# SCH9_BBB_Eth.net
KiCad netlist of a schematic drawn in Altium Designer
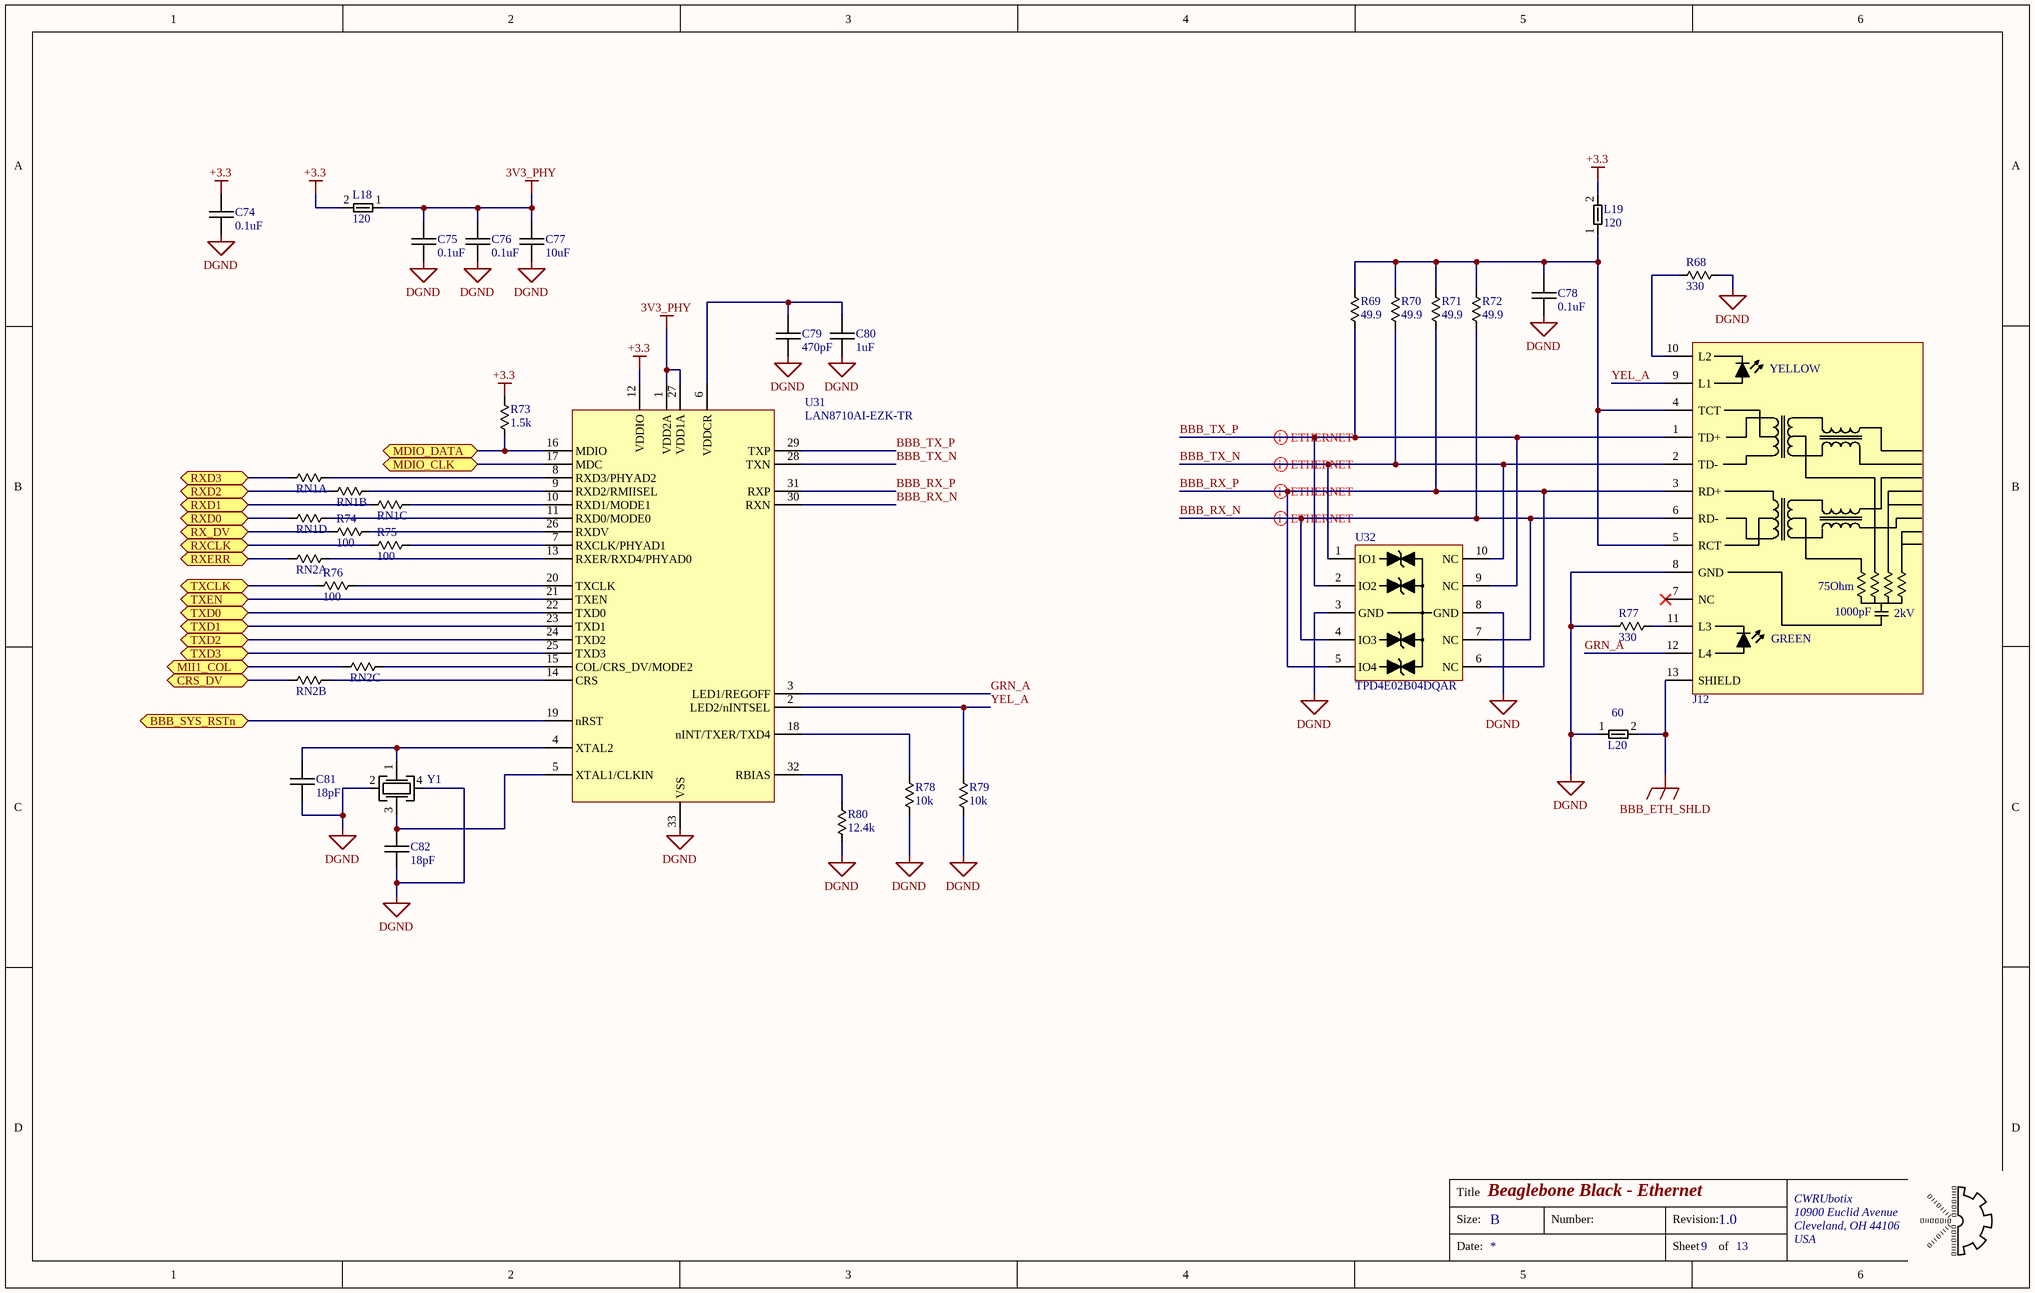
[diagram p0: SCH9_BBB_Eth.SchDoc]

(export (version "E")
  (design (tool "Eeschema 10.0.6"))
  (components
    (comp (ref "C74")
      (value "0.1uF")
      (footprint "chip_0603")
      (description "CAP, 0.1uF, ±10%, 16V, X7R, 0603")
      (fields (field (name "PART NUMBER") "CAP-00542") (field (name "TOLERANCE") "±10%"))
      (libsource (lib "Capacitors$") (part "CAP-00542"))
    )
    (comp (ref "C75")
      (value "0.1uF")
      (footprint "chip_0603")
      (description "CAP, 0.1uF, ±10%, 16V, X7R, 0603")
      (fields (field (name "PART NUMBER") "CAP-00542") (field (name "TOLERANCE") "±10%"))
      (libsource (lib "Capacitors$") (part "CAP-00542"))
    )
    (comp (ref "C76")
      (value "0.1uF")
      (footprint "chip_0603")
      (description "CAP, 0.1uF, ±10%, 16V, X7R, 0603")
      (fields (field (name "PART NUMBER") "CAP-00542") (field (name "TOLERANCE") "±10%"))
      (libsource (lib "Capacitors$") (part "CAP-00542"))
    )
    (comp (ref "C77")
      (value "10uF")
      (footprint "chip_1206")
      (description "CAP, 10uF, ±10%, 25V, X7R, 1206")
      (fields (field (name "PART NUMBER") "CAP-00539") (field (name "TOLERANCE") "±10%"))
      (libsource (lib "Capacitors$") (part "CAP-00539"))
    )
    (comp (ref "C78")
      (value "0.1uF")
      (footprint "chip_0603")
      (description "CAP, 0.1uF, ±10%, 16V, X7R, 0603")
      (fields (field (name "PART NUMBER") "CAP-00542") (field (name "TOLERANCE") "±10%"))
      (libsource (lib "Capacitors$") (part "CAP-00542"))
    )
    (comp (ref "C79")
      (value "470pF")
      (footprint "chip_0603")
      (description "CAP, 470pF, ±2%, 50V, C0G, 0603")
      (fields (field (name "PART NUMBER") "CAP-00429") (field (name "TOLERANCE") "±2%"))
      (libsource (lib "Capacitors$") (part "CAP-00429"))
    )
    (comp (ref "C80")
      (value "1uF")
      (footprint "chip_0805")
      (description "CAP, 1uF, 10%, 16V, X7R, 0805")
      (fields (field (name "PART NUMBER") "CAP-00110") (field (name "TOLERANCE") "10%"))
      (libsource (lib "Capacitors$") (part "CAP-00110"))
    )
    (comp (ref "C81")
      (value "18pF")
      (footprint "chip_0603")
      (description "CAP, 18pF, ±2%, 50V, C0G, 0603")
      (fields (field (name "PART NUMBER") "CAP-00409") (field (name "TOLERANCE") "±2%"))
      (libsource (lib "Capacitors$") (part "CAP-00409"))
    )
    (comp (ref "C82")
      (value "18pF")
      (footprint "chip_0603")
      (description "CAP, 18pF, ±2%, 50V, C0G, 0603")
      (fields (field (name "PART NUMBER") "CAP-00409") (field (name "TOLERANCE") "±2%"))
      (libsource (lib "Capacitors$") (part "CAP-00409"))
    )
    (comp (ref "J12")
      (value "amphenol-RJMG1B")
      (footprint "AMPHENOL_RJMG1B")
      (description "RJ45 Modular Mag-Jack, 8P8C, 10/100 Base-T")
      (fields (field (name "PART NUMBER") "CONN-00057") (field (name "MANUFACTURER") "Amphenol"))
      (libsource (lib "Connectors$") (part "CONN-00057"))
    )
    (comp (ref "L18")
      (value "bead_0")
      (footprint "CHIP_0603_FE")
      (description "Fe Bead, 120 @ 100MHz, 800mA, 0603")
      (fields
        (field (name "PART NUMBER") "MAG-00126")
        (field (name "IMPEDANCE") "120")
        (field (name "MANUFACTURER") "Murata")
      )
      (libsource (lib "Magnetics$") (part "MAG-00126"))
    )
    (comp (ref "L19")
      (value "bead_0")
      (footprint "CHIP_0603_FE")
      (description "Fe Bead, 120 @ 100MHz, 800mA, 0603")
      (fields
        (field (name "PART NUMBER") "MAG-00126")
        (field (name "IMPEDANCE") "120")
        (field (name "MANUFACTURER") "Murata")
      )
      (libsource (lib "Magnetics$") (part "MAG-00126"))
    )
    (comp (ref "L20")
      (value "bead_0")
      (footprint "CHIP_0805_FE")
      (description "Fe Bead, 60 @ 100MH, 3A, 0805")
      (fields
        (field (name "PART NUMBER") "MAG-00125")
        (field (name "IMPEDANCE") "60")
        (field (name "MANUFACTURER") "Pulse Electronics")
      )
      (libsource (lib "Magnetics$") (part "MAG-00125"))
    )
    (comp (ref "R68")
      (value "330")
      (footprint "chip_0603")
      (description "RES SMD 330 OHM 1% 1/4W 0603")
      (fields (field (name "PART NUMBER") "RES-00221") (field (name "TOLERANCE") "1%"))
      (libsource (lib "Resistors$") (part "RES-00221"))
    )
    (comp (ref "R69")
      (value "49.9")
      (footprint "chip_0603")
      (description "RES SMD 49.9 OHM 1% 1/10W 0603")
      (fields (field (name "PART NUMBER") "RES-00705") (field (name "TOLERANCE") "1%"))
      (libsource (lib "Resistors$") (part "RES-00705"))
    )
    (comp (ref "R70")
      (value "49.9")
      (footprint "chip_0603")
      (description "RES SMD 49.9 OHM 1% 1/10W 0603")
      (fields (field (name "PART NUMBER") "RES-00705") (field (name "TOLERANCE") "1%"))
      (libsource (lib "Resistors$") (part "RES-00705"))
    )
    (comp (ref "R71")
      (value "49.9")
      (footprint "chip_0603")
      (description "RES SMD 49.9 OHM 1% 1/10W 0603")
      (fields (field (name "PART NUMBER") "RES-00705") (field (name "TOLERANCE") "1%"))
      (libsource (lib "Resistors$") (part "RES-00705"))
    )
    (comp (ref "R72")
      (value "49.9")
      (footprint "chip_0603")
      (description "RES SMD 49.9 OHM 1% 1/10W 0603")
      (fields (field (name "PART NUMBER") "RES-00705") (field (name "TOLERANCE") "1%"))
      (libsource (lib "Resistors$") (part "RES-00705"))
    )
    (comp (ref "R73")
      (value "1.5k")
      (footprint "chip_0603")
      (description "RES SMD 1.5K OHM 1% 1/4W 0603")
      (fields (field (name "PART NUMBER") "RES-00284") (field (name "TOLERANCE") "1%"))
      (libsource (lib "Resistors$") (part "RES-00284"))
    )
    (comp (ref "R74")
      (value "100")
      (footprint "chip_0603")
      (description "RES SMD 100 OHM 1% 1/4W 0603")
      (fields (field (name "PART NUMBER") "RES-00178") (field (name "TOLERANCE") "1%"))
      (libsource (lib "Resistors$") (part "RES-00178"))
    )
    (comp (ref "R75")
      (value "100")
      (footprint "chip_0603")
      (description "RES SMD 100 OHM 1% 1/4W 0603")
      (fields (field (name "PART NUMBER") "RES-00178") (field (name "TOLERANCE") "1%"))
      (libsource (lib "Resistors$") (part "RES-00178"))
    )
    (comp (ref "R76")
      (value "100")
      (footprint "chip_0603")
      (description "RES SMD 100 OHM 1% 1/4W 0603")
      (fields (field (name "PART NUMBER") "RES-00178") (field (name "TOLERANCE") "1%"))
      (libsource (lib "Resistors$") (part "RES-00178"))
    )
    (comp (ref "R77")
      (value "330")
      (footprint "chip_0603")
      (description "RES SMD 330 OHM 1% 1/4W 0603")
      (fields (field (name "PART NUMBER") "RES-00221") (field (name "TOLERANCE") "1%"))
      (libsource (lib "Resistors$") (part "RES-00221"))
    )
    (comp (ref "R78")
      (value "10k")
      (footprint "chip_0603")
      (description "RES SMD 10K OHM 1% 1/4W 0603")
      (fields (field (name "PART NUMBER") "RES-00306") (field (name "TOLERANCE") "1%"))
      (libsource (lib "Resistors$") (part "RES-00306"))
    )
    (comp (ref "R79")
      (value "10k")
      (footprint "chip_0603")
      (description "RES SMD 10K OHM 1% 1/4W 0603")
      (fields (field (name "PART NUMBER") "RES-00306") (field (name "TOLERANCE") "1%"))
      (libsource (lib "Resistors$") (part "RES-00306"))
    )
    (comp (ref "R80")
      (value "12.4k")
      (footprint "chip_0603")
      (description "RES SMD 12.4K OHM 1% 1/10W 0603")
      (fields (field (name "PART NUMBER") "RES-00721") (field (name "TOLERANCE") "1%"))
      (libsource (lib "Resistors$") (part "RES-00721"))
    )
    (comp (ref "RN1")
      (value "res_array_4")
      (footprint "chip_1206_arr")
      (description "RES ARRAY 4 RES 100 OHM 5% 62.5mW 1206")
      (fields (field (name "PART NUMBER") "RES-00723") (field (name "TOLERANCE") "5%"))
      (libsource (lib "Resistors$") (part "RES-00723"))
    )
    (comp (ref "RN2")
      (value "res_array_4")
      (footprint "chip_1206_arr")
      (description "RES ARRAY 4 RES 100 OHM 5% 62.5mW 1206")
      (fields (field (name "PART NUMBER") "RES-00723") (field (name "TOLERANCE") "5%"))
      (libsource (lib "Resistors$") (part "RES-00723"))
    )
    (comp (ref "U31")
      (value "LAN8710AI-EZK-TR")
      (footprint "QFN-32-EP")
      (description "IC, 10/100 Ethernet Transceiver")
      (fields (field (name "PART NUMBER") "IFACE-00025") (field (name "MANUFACTURER") "Microchip"))
      (libsource (lib "Interfaces$") (part "IFACE-00025"))
    )
    (comp (ref "U32")
      (value "TPD4E02B04DQAR")
      (footprint "USON-10")
      (description "TVS, 4-Ch, ESD Protec, 3.6V 8.8V 10-USON")
      (fields (field (name "PART NUMBER") "DIO-00068") (field (name "MANUFACTURER") "TI"))
      (libsource (lib "Diodes$") (part "DIO-00068"))
    )
    (comp (ref "Y1")
      (value "osc_xtal_4p_1-3")
      (footprint "ECX-32")
      (description "XTAL, 25MHz, 20pF, 20ppm")
      (fields (field (name "PART NUMBER") "OSC-00005") (field (name "TOLERANCE") "20ppm"))
      (libsource (lib "Oscillators$") (part "OSC-00005"))
    )
  )
  (nets
    (net (code "1") (name "+3.3") (class "Default")
      (node (ref "C74") (pin "2") (pinfunction "2_2") (pintype "passive"))
      (node (ref "L18") (pin "2") (pinfunction "2_2") (pintype "passive"))
      (node (ref "L19") (pin "2") (pinfunction "2_2") (pintype "passive"))
      (node (ref "R73") (pin "1") (pinfunction "1_1") (pintype "passive"))
      (node (ref "U31") (pin "12") (pinfunction "VDDIO_12") (pintype "passive"))
    )
    (net (code "2") (name "/BBB_RX_N") (class "Default")
      (node (ref "J12") (pin "6") (pinfunction "RD-_6") (pintype "passive"))
      (node (ref "R72") (pin "2") (pinfunction "2_2") (pintype "passive"))
      (node (ref "U31") (pin "30") (pinfunction "RXN_30") (pintype "passive"))
      (node (ref "U32") (pin "4") (pinfunction "IO3_4") (pintype "passive"))
      (node (ref "U32") (pin "7") (pinfunction "NC_7") (pintype "passive"))
    )
    (net (code "3") (name "/BBB_RX_P") (class "Default")
      (node (ref "J12") (pin "3") (pinfunction "RD+_3") (pintype "passive"))
      (node (ref "R71") (pin "2") (pinfunction "2_2") (pintype "passive"))
      (node (ref "U31") (pin "31") (pinfunction "RXP_31") (pintype "passive"))
      (node (ref "U32") (pin "5") (pinfunction "IO4_5") (pintype "passive"))
      (node (ref "U32") (pin "6") (pinfunction "NC_6") (pintype "passive"))
    )
    (net (code "4") (name "/BBB_SYS_RSTn") (class "Default")
      (node (ref "U31") (pin "19") (pinfunction "nRST_19") (pintype "passive"))
    )
    (net (code "5") (name "/BBB_TX_N") (class "Default")
      (node (ref "J12") (pin "2") (pinfunction "TD-_2") (pintype "passive"))
      (node (ref "R70") (pin "2") (pinfunction "2_2") (pintype "passive"))
      (node (ref "U31") (pin "28") (pinfunction "TXN_28") (pintype "passive"))
      (node (ref "U32") (pin "1") (pinfunction "IO1_1") (pintype "passive"))
      (node (ref "U32") (pin "10") (pinfunction "NC_10") (pintype "passive"))
    )
    (net (code "6") (name "/BBB_TX_P") (class "Default")
      (node (ref "J12") (pin "1") (pinfunction "TD+_1") (pintype "passive"))
      (node (ref "R69") (pin "2") (pinfunction "2_2") (pintype "passive"))
      (node (ref "U31") (pin "29") (pinfunction "TXP_29") (pintype "passive"))
      (node (ref "U32") (pin "2") (pinfunction "IO2_2") (pintype "passive"))
      (node (ref "U32") (pin "9") (pinfunction "NC_9") (pintype "passive"))
    )
    (net (code "7") (name "/CRS_DV") (class "Default")
      (node (ref "RN2") (pin "2") (pinfunction "2_2") (pintype "passive"))
    )
    (net (code "8") (name "/GRN_A") (class "Default")
      (node (ref "J12") (pin "12") (pinfunction "L4_12") (pintype "passive"))
      (node (ref "U31") (pin "3") (pinfunction "LED1/REGOFF_3") (pintype "passive"))
    )
    (net (code "9") (name "/MDIO_CLK") (class "Default")
      (node (ref "U31") (pin "17") (pinfunction "MDC_17") (pintype "passive"))
    )
    (net (code "10") (name "/MDIO_DATA") (class "Default")
      (node (ref "R73") (pin "2") (pinfunction "2_2") (pintype "passive"))
      (node (ref "U31") (pin "16") (pinfunction "MDIO_16") (pintype "passive"))
    )
    (net (code "11") (name "/MII1_COL") (class "Default")
      (node (ref "RN2") (pin "3") (pinfunction "3_3") (pintype "passive"))
    )
    (net (code "12") (name "/RXCLK") (class "Default")
      (node (ref "R75") (pin "1") (pinfunction "1_1") (pintype "passive"))
    )
    (net (code "13") (name "/RXD0") (class "Default")
      (node (ref "RN1") (pin "4") (pinfunction "4_4") (pintype "passive"))
    )
    (net (code "14") (name "/RXD1") (class "Default")
      (node (ref "RN1") (pin "3") (pinfunction "3_3") (pintype "passive"))
    )
    (net (code "15") (name "/RXD2") (class "Default")
      (node (ref "RN1") (pin "2") (pinfunction "2_2") (pintype "passive"))
    )
    (net (code "16") (name "/RXD3") (class "Default")
      (node (ref "RN1") (pin "1") (pinfunction "1_1") (pintype "passive"))
    )
    (net (code "17") (name "/RXERR") (class "Default")
      (node (ref "RN2") (pin "1") (pinfunction "1_1") (pintype "passive"))
    )
    (net (code "18") (name "/RX_DV") (class "Default")
      (node (ref "R74") (pin "1") (pinfunction "1_1") (pintype "passive"))
    )
    (net (code "19") (name "/TXCLK") (class "Default")
      (node (ref "R76") (pin "1") (pinfunction "1_1") (pintype "passive"))
    )
    (net (code "20") (name "/TXD0") (class "Default")
      (node (ref "U31") (pin "22") (pinfunction "TXD0_22") (pintype "passive"))
    )
    (net (code "21") (name "/TXD1") (class "Default")
      (node (ref "U31") (pin "23") (pinfunction "TXD1_23") (pintype "passive"))
    )
    (net (code "22") (name "/TXD2") (class "Default")
      (node (ref "U31") (pin "24") (pinfunction "TXD2_24") (pintype "passive"))
    )
    (net (code "23") (name "/TXD3") (class "Default")
      (node (ref "U31") (pin "25") (pinfunction "TXD3_25") (pintype "passive"))
    )
    (net (code "24") (name "/TXEN") (class "Default")
      (node (ref "U31") (pin "21") (pinfunction "TXEN_21") (pintype "passive"))
    )
    (net (code "25") (name "/YEL_A") (class "Default")
      (node (ref "J12") (pin "9") (pinfunction "L1_9") (pintype "passive"))
      (node (ref "R79") (pin "1") (pinfunction "1_1") (pintype "passive"))
      (node (ref "U31") (pin "2") (pinfunction "LED2/nINTSEL_2") (pintype "passive"))
    )
    (net (code "26") (name "3V3_PHY") (class "Default")
      (node (ref "C75") (pin "2") (pinfunction "2_2") (pintype "passive"))
      (node (ref "C76") (pin "2") (pinfunction "2_2") (pintype "passive"))
      (node (ref "C77") (pin "1") (pinfunction "1_1") (pintype "passive"))
      (node (ref "L18") (pin "1") (pinfunction "1_1") (pintype "passive"))
      (node (ref "U31") (pin "1") (pinfunction "VDD2A_1") (pintype "passive"))
      (node (ref "U31") (pin "27") (pinfunction "VDD1A_27") (pintype "passive"))
    )
    (net (code "27") (name "BBB_ETH_SHLD") (class "Default")
      (node (ref "J12") (pin "13") (pinfunction "SHIELD_13") (pintype "passive"))
      (node (ref "L20") (pin "2") (pinfunction "2_2") (pintype "passive"))
    )
    (net (code "28") (name "DGND") (class "Default")
      (node (ref "C74") (pin "1") (pinfunction "1_1") (pintype "passive"))
      (node (ref "C75") (pin "1") (pinfunction "1_1") (pintype "passive"))
      (node (ref "C76") (pin "1") (pinfunction "1_1") (pintype "passive"))
      (node (ref "C77") (pin "2") (pinfunction "2_2") (pintype "passive"))
      (node (ref "C78") (pin "1") (pinfunction "1_1") (pintype "passive"))
      (node (ref "C79") (pin "2") (pinfunction "2_2") (pintype "passive"))
      (node (ref "C80") (pin "2") (pinfunction "2_2") (pintype "passive"))
      (node (ref "C81") (pin "2") (pinfunction "2_2") (pintype "passive"))
      (node (ref "C82") (pin "2") (pinfunction "2_2") (pintype "passive"))
      (node (ref "J12") (pin "8") (pinfunction "GND_8") (pintype "passive"))
      (node (ref "L20") (pin "1") (pinfunction "1_1") (pintype "passive"))
      (node (ref "R68") (pin "1") (pinfunction "1_1") (pintype "passive"))
      (node (ref "R77") (pin "2") (pinfunction "2_2") (pintype "passive"))
      (node (ref "R78") (pin "2") (pinfunction "2_2") (pintype "passive"))
      (node (ref "R79") (pin "2") (pinfunction "2_2") (pintype "passive"))
      (node (ref "R80") (pin "2") (pinfunction "2_2") (pintype "passive"))
      (node (ref "U31") (pin "33") (pinfunction "VSS_33") (pintype "passive"))
      (node (ref "U32") (pin "3") (pinfunction "GND_3") (pintype "passive"))
      (node (ref "U32") (pin "8") (pinfunction "GND_8") (pintype "passive"))
      (node (ref "Y1") (pin "2") (pinfunction "GND_2") (pintype "passive"))
      (node (ref "Y1") (pin "4") (pinfunction "GND_4") (pintype "passive"))
    )
    (net (code "29") (name "Net-(J12-L2)") (class "Default")
      (node (ref "J12") (pin "10") (pinfunction "L2_10") (pintype "passive"))
      (node (ref "R68") (pin "2") (pinfunction "2_2") (pintype "passive"))
    )
    (net (code "30") (name "Net-(J12-L3)") (class "Default")
      (node (ref "J12") (pin "11") (pinfunction "L3_11") (pintype "passive"))
      (node (ref "R77") (pin "1") (pinfunction "1_1") (pintype "passive"))
    )
    (net (code "31") (name "Net-(J12-RCT)") (class "Default")
      (node (ref "C78") (pin "2") (pinfunction "2_2") (pintype "passive"))
      (node (ref "J12") (pin "4") (pinfunction "TCT_4") (pintype "passive"))
      (node (ref "J12") (pin "5") (pinfunction "RCT_5") (pintype "passive"))
      (node (ref "L19") (pin "1") (pinfunction "1_1") (pintype "passive"))
      (node (ref "R69") (pin "1") (pinfunction "1_1") (pintype "passive"))
      (node (ref "R70") (pin "1") (pinfunction "1_1") (pintype "passive"))
      (node (ref "R71") (pin "1") (pinfunction "1_1") (pintype "passive"))
      (node (ref "R72") (pin "1") (pinfunction "1_1") (pintype "passive"))
    )
    (net (code "32") (name "Net-(U31-COL{slash}CRS_DV{slash}MODE2)") (class "Default")
      (node (ref "RN2") (pin "6") (pinfunction "6_6") (pintype "passive"))
      (node (ref "U31") (pin "15") (pinfunction "COL/CRS_DV/MODE2_15") (pintype "passive"))
    )
    (net (code "33") (name "Net-(U31-CRS)") (class "Default")
      (node (ref "RN2") (pin "7") (pinfunction "7_7") (pintype "passive"))
      (node (ref "U31") (pin "14") (pinfunction "CRS_14") (pintype "passive"))
    )
    (net (code "34") (name "Net-(U31-RBIAS)") (class "Default")
      (node (ref "R80") (pin "1") (pinfunction "1_1") (pintype "passive"))
      (node (ref "U31") (pin "32") (pinfunction "RBIAS_32") (pintype "passive"))
    )
    (net (code "35") (name "Net-(U31-RXCLK{slash}PHYAD1)") (class "Default")
      (node (ref "R75") (pin "2") (pinfunction "2_2") (pintype "passive"))
      (node (ref "U31") (pin "7") (pinfunction "RXCLK/PHYAD1_7") (pintype "passive"))
    )
    (net (code "36") (name "Net-(U31-RXD0{slash}MODE0)") (class "Default")
      (node (ref "RN1") (pin "5") (pinfunction "5_5") (pintype "passive"))
      (node (ref "U31") (pin "11") (pinfunction "RXD0/MODE0_11") (pintype "passive"))
    )
    (net (code "37") (name "Net-(U31-RXD1{slash}MODE1)") (class "Default")
      (node (ref "RN1") (pin "6") (pinfunction "6_6") (pintype "passive"))
      (node (ref "U31") (pin "10") (pinfunction "RXD1/MODE1_10") (pintype "passive"))
    )
    (net (code "38") (name "Net-(U31-RXD2{slash}RMIISEL)") (class "Default")
      (node (ref "RN1") (pin "7") (pinfunction "7_7") (pintype "passive"))
      (node (ref "U31") (pin "9") (pinfunction "RXD2/RMIISEL_9") (pintype "passive"))
    )
    (net (code "39") (name "Net-(U31-RXD3{slash}PHYAD2)") (class "Default")
      (node (ref "RN1") (pin "8") (pinfunction "8_8") (pintype "passive"))
      (node (ref "U31") (pin "8") (pinfunction "RXD3/PHYAD2_8") (pintype "passive"))
    )
    (net (code "40") (name "Net-(U31-RXDV)") (class "Default")
      (node (ref "R74") (pin "2") (pinfunction "2_2") (pintype "passive"))
      (node (ref "U31") (pin "26") (pinfunction "RXDV_26") (pintype "passive"))
    )
    (net (code "41") (name "Net-(U31-RXER{slash}RXD4{slash}PHYAD0)") (class "Default")
      (node (ref "RN2") (pin "8") (pinfunction "8_8") (pintype "passive"))
      (node (ref "U31") (pin "13") (pinfunction "RXER/RXD4/PHYAD0_13") (pintype "passive"))
    )
    (net (code "42") (name "Net-(U31-TXCLK)") (class "Default")
      (node (ref "R76") (pin "2") (pinfunction "2_2") (pintype "passive"))
      (node (ref "U31") (pin "20") (pinfunction "TXCLK_20") (pintype "passive"))
    )
    (net (code "43") (name "Net-(U31-VDDCR)") (class "Default")
      (node (ref "C79") (pin "1") (pinfunction "1_1") (pintype "passive"))
      (node (ref "C80") (pin "1") (pinfunction "1_1") (pintype "passive"))
      (node (ref "U31") (pin "6") (pinfunction "VDDCR_6") (pintype "passive"))
    )
    (net (code "44") (name "Net-(U31-XTAL1{slash}CLKIN)") (class "Default")
      (node (ref "C82") (pin "1") (pinfunction "1_1") (pintype "passive"))
      (node (ref "U31") (pin "5") (pinfunction "XTAL1/CLKIN_5") (pintype "passive"))
      (node (ref "Y1") (pin "3") (pinfunction "3_3") (pintype "passive"))
    )
    (net (code "45") (name "Net-(U31-XTAL2)") (class "Default")
      (node (ref "C81") (pin "1") (pinfunction "1_1") (pintype "passive"))
      (node (ref "U31") (pin "4") (pinfunction "XTAL2_4") (pintype "passive"))
      (node (ref "Y1") (pin "1") (pinfunction "1_1") (pintype "passive"))
    )
    (net (code "46") (name "Net-(U31-nINT{slash}TXER{slash}TXD4)") (class "Default")
      (node (ref "R78") (pin "1") (pinfunction "1_1") (pintype "passive"))
      (node (ref "U31") (pin "18") (pinfunction "nINT/TXER/TXD4_18") (pintype "passive"))
    )
    (net (code "47") (name "unconnected-(J12-NC-Pad7)") (class "Default")
      (node (ref "J12") (pin "7") (pinfunction "NC_7") (pintype "passive+no_connect"))
    )
  )
)
